# arduino-nano-dcc-v2.net
KiCad netlist of a schematic drawn in EAGLE
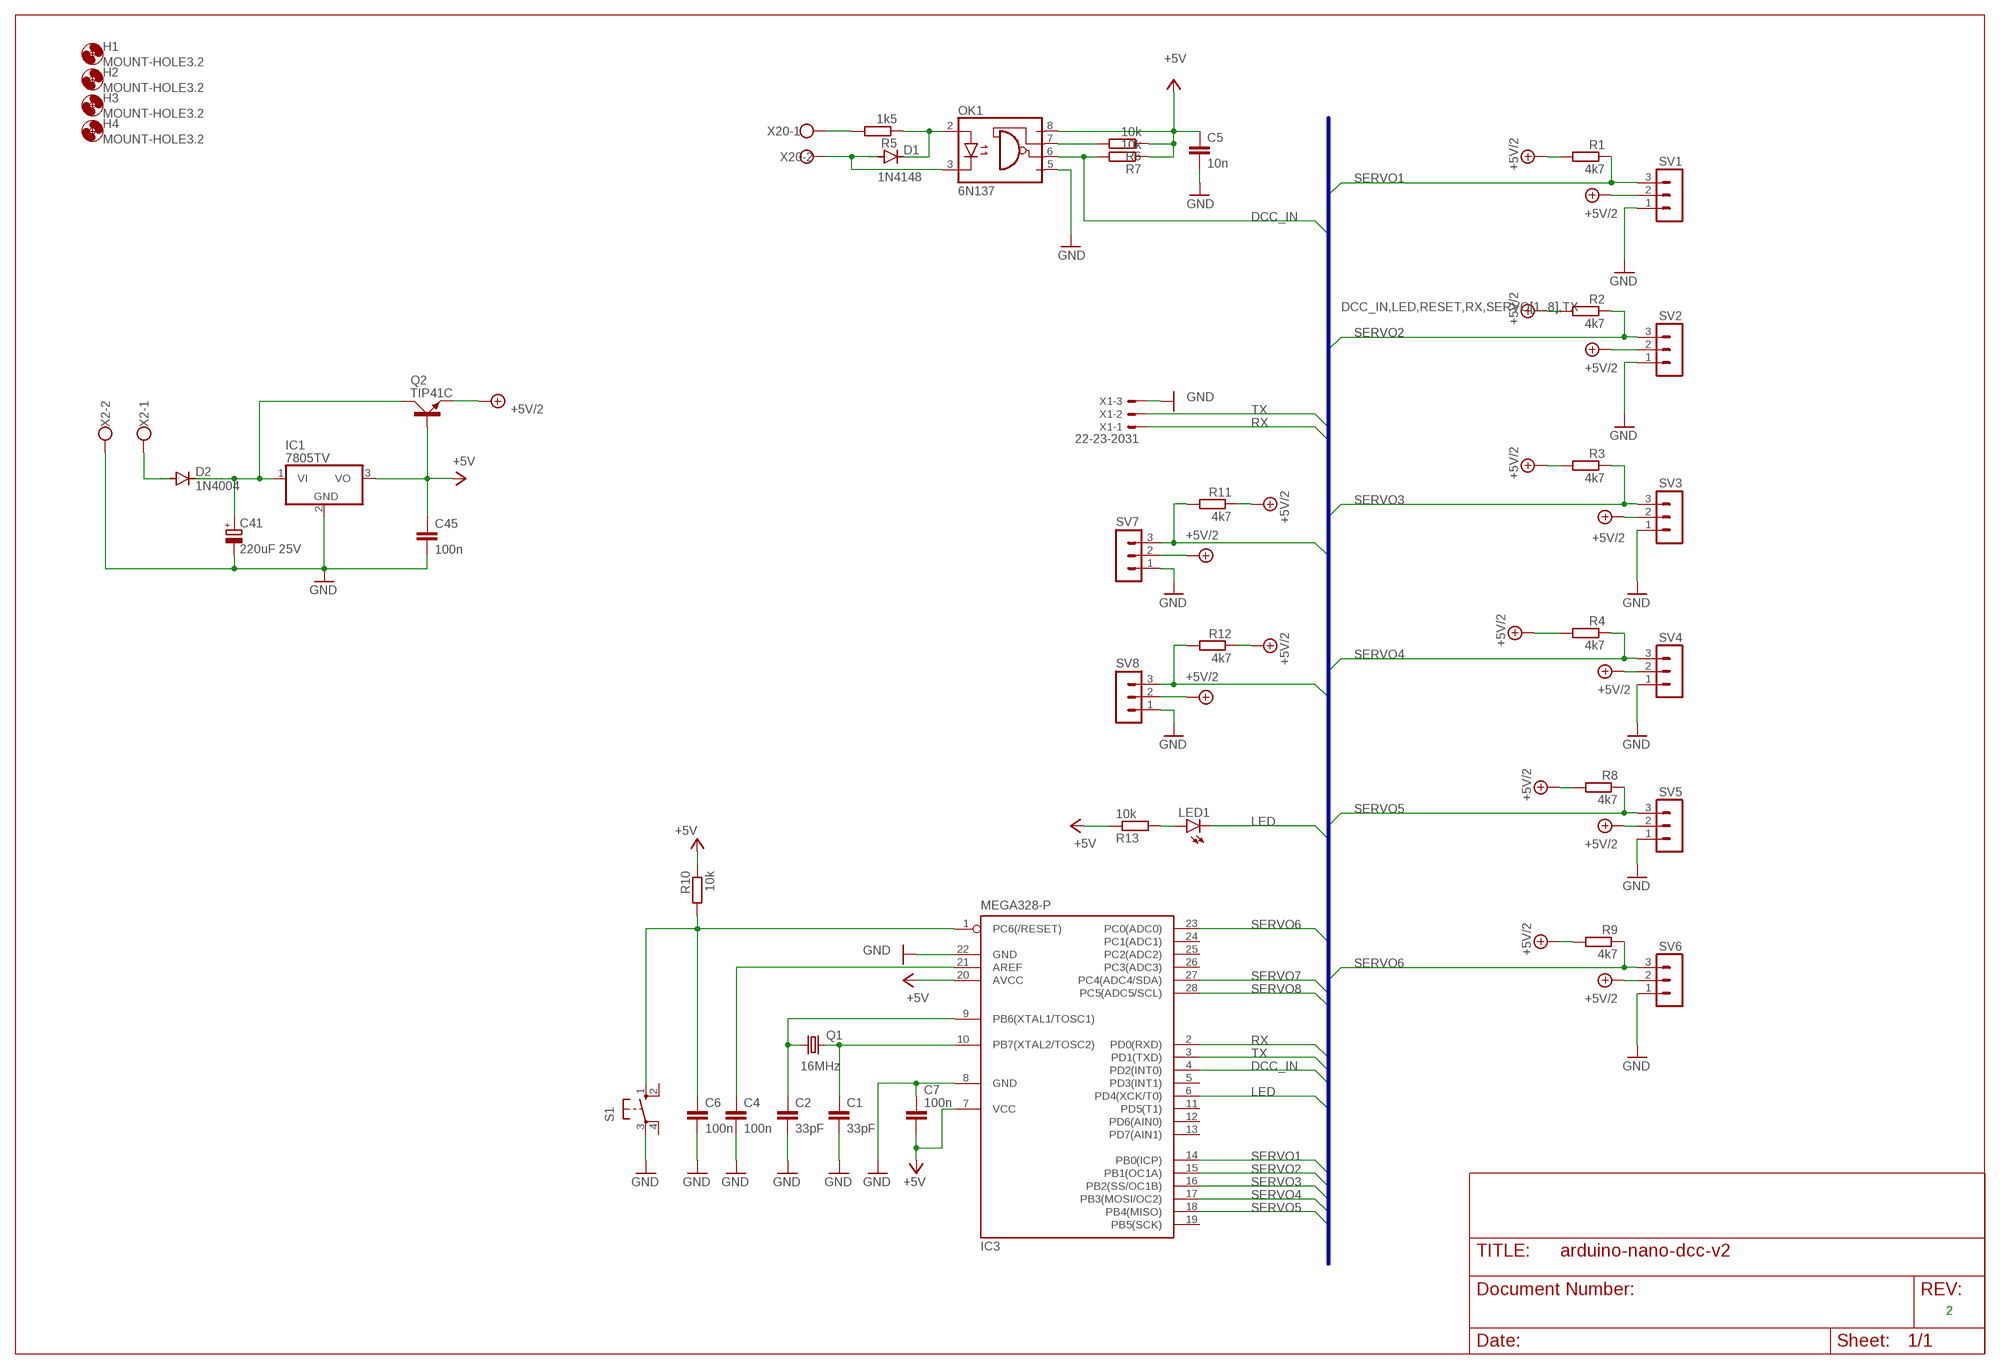
[diagram p0: schematic, sheet 1]

(export (version "E")
  (design (tool "Eeschema 10.0.6"))
  (components
    (comp (ref "C1")
      (value "33pF")
      (footprint "eagle-import:C025-024X044")
      (libsource (lib "eagle-import") (part "rcl_334_C-EU025-024X044"))
    )
    (comp (ref "C2")
      (value "33pF")
      (footprint "eagle-import:C025-024X044")
      (libsource (lib "eagle-import") (part "rcl_334_C-EU025-024X044"))
    )
    (comp (ref "C4")
      (value "100n")
      (footprint "eagle-import:C050-024X044")
      (libsource (lib "eagle-import") (part "rcl_334_C-EU050-024X044"))
    )
    (comp (ref "C5")
      (value "10n")
      (footprint "eagle-import:C050-024X044")
      (libsource (lib "eagle-import") (part "C-EU050-024X044"))
    )
    (comp (ref "C6")
      (value "100n")
      (footprint "eagle-import:C050-024X044")
      (libsource (lib "eagle-import") (part "rcl_334_C-EU050-024X044"))
    )
    (comp (ref "C7")
      (value "100n")
      (footprint "eagle-import:C050-024X044")
      (libsource (lib "eagle-import") (part "rcl_334_C-EU050-024X044"))
    )
    (comp (ref "C41")
      (value "220uF 25V")
      (footprint "eagle-import:E5-8,5")
      (libsource (lib "eagle-import") (part "CPOL-EUE5-8.5"))
    )
    (comp (ref "C45")
      (value "100n")
      (footprint "eagle-import:C050-024X044")
      (libsource (lib "eagle-import") (part "C-EU050-024X044"))
    )
    (comp (ref "D1")
      (value "1N4148")
      (footprint "eagle-import:DO35-7")
      (libsource (lib "eagle-import") (part "1N4148DO35-7"))
    )
    (comp (ref "D2")
      (value "1N4004")
      (footprint "eagle-import:DO41-10")
      (libsource (lib "eagle-import") (part "1N4004"))
    )
    (comp (ref "H1")
      (value "MOUNT-HOLE3.2")
      (footprint "eagle-import:3,2")
      (libsource (lib "eagle-import") (part "MOUNT-HOLE3.2"))
    )
    (comp (ref "H2")
      (value "MOUNT-HOLE3.2")
      (footprint "eagle-import:3,2")
      (libsource (lib "eagle-import") (part "MOUNT-HOLE3.2"))
    )
    (comp (ref "H3")
      (value "MOUNT-HOLE3.2")
      (footprint "eagle-import:3,2")
      (libsource (lib "eagle-import") (part "MOUNT-HOLE3.2"))
    )
    (comp (ref "H4")
      (value "MOUNT-HOLE3.2")
      (footprint "eagle-import:3,2")
      (libsource (lib "eagle-import") (part "MOUNT-HOLE3.2"))
    )
    (comp (ref "IC1")
      (value "7805TV")
      (footprint "eagle-import:TO220V")
      (libsource (lib "eagle-import") (part "78TV05"))
    )
    (comp (ref "IC3")
      (value "MEGA328-P")
      (footprint "eagle-import:DIL28-3")
      (libsource (lib "eagle-import") (part "MEGA8-P"))
    )
    (comp (ref "LED1")
      (value "LED3MM")
      (footprint "eagle-import:LED3MM")
      (libsource (lib "eagle-import") (part "LED3MM"))
    )
    (comp (ref "OK1")
      (value "6N137")
      (footprint "eagle-import:DIL08")
      (libsource (lib "eagle-import") (part "6N137"))
    )
    (comp (ref "Q1")
      (value "16MHz")
      (footprint "eagle-import:HC49U-V")
      (libsource (lib "eagle-import") (part "CRYSTALHC49U-V"))
    )
    (comp (ref "Q2")
      (value "TIP41C")
      (footprint "eagle-import:TO220AV")
      (libsource (lib "eagle-import") (part "TIP41C"))
    )
    (comp (ref "R1")
      (value "4k7")
      (footprint "eagle-import:0204_7")
      (libsource (lib "eagle-import") (part "R-EU_0204/7"))
    )
    (comp (ref "R2")
      (value "4k7")
      (footprint "eagle-import:0204_7")
      (libsource (lib "eagle-import") (part "R-EU_0204/7"))
    )
    (comp (ref "R3")
      (value "4k7")
      (footprint "eagle-import:0204_7")
      (libsource (lib "eagle-import") (part "R-EU_0204/7"))
    )
    (comp (ref "R4")
      (value "4k7")
      (footprint "eagle-import:0204_7")
      (libsource (lib "eagle-import") (part "R-EU_0204/7"))
    )
    (comp (ref "R5")
      (value "1k5")
      (footprint "eagle-import:0204_7")
      (libsource (lib "eagle-import") (part "R-EU_0204/7"))
    )
    (comp (ref "R6")
      (value "10k")
      (footprint "eagle-import:0204_7")
      (libsource (lib "eagle-import") (part "R-EU_0204/7"))
    )
    (comp (ref "R7")
      (value "10k")
      (footprint "eagle-import:0204_7")
      (libsource (lib "eagle-import") (part "R-EU_0204/7"))
    )
    (comp (ref "R8")
      (value "4k7")
      (footprint "eagle-import:0204_7")
      (libsource (lib "eagle-import") (part "R-EU_0204/7"))
    )
    (comp (ref "R9")
      (value "4k7")
      (footprint "eagle-import:0204_7")
      (libsource (lib "eagle-import") (part "R-EU_0204/7"))
    )
    (comp (ref "R10")
      (value "10k")
      (footprint "eagle-import:0204_7")
      (libsource (lib "eagle-import") (part "R-EU_0204/7"))
    )
    (comp (ref "R11")
      (value "4k7")
      (footprint "eagle-import:0204_7")
      (libsource (lib "eagle-import") (part "R-EU_0204/7"))
    )
    (comp (ref "R12")
      (value "4k7")
      (footprint "eagle-import:0204_5")
      (libsource (lib "eagle-import") (part "R-EU_0204/5"))
    )
    (comp (ref "R13")
      (value "10k")
      (footprint "eagle-import:0204V")
      (libsource (lib "eagle-import") (part "R-EU_0204/2V"))
    )
    (comp (ref "S1")
      (value "10-XX")
      (footprint "eagle-import:B3F-10XX")
      (fields (field (name "MPN") "B3F-1000"))
      (libsource (lib "eagle-import") (part "10-XX"))
    )
    (comp (ref "SV1")
      (value "MA03-1")
      (footprint "eagle-import:MA03-1")
      (libsource (lib "eagle-import") (part "MA03-1"))
    )
    (comp (ref "SV2")
      (value "MA03-1")
      (footprint "eagle-import:MA03-1")
      (libsource (lib "eagle-import") (part "MA03-1"))
    )
    (comp (ref "SV3")
      (value "MA03-1")
      (footprint "eagle-import:MA03-1")
      (libsource (lib "eagle-import") (part "MA03-1"))
    )
    (comp (ref "SV4")
      (value "MA03-1")
      (footprint "eagle-import:MA03-1")
      (libsource (lib "eagle-import") (part "MA03-1"))
    )
    (comp (ref "SV5")
      (value "MA03-1")
      (footprint "eagle-import:MA03-1")
      (libsource (lib "eagle-import") (part "MA03-1"))
    )
    (comp (ref "SV6")
      (value "MA03-1")
      (footprint "eagle-import:MA03-1")
      (libsource (lib "eagle-import") (part "MA03-1"))
    )
    (comp (ref "SV7")
      (value "MA03-1")
      (footprint "eagle-import:MA03-1")
      (libsource (lib "eagle-import") (part "MA03-1"))
    )
    (comp (ref "SV8")
      (value "MA03-1")
      (footprint "eagle-import:MA03-1")
      (libsource (lib "eagle-import") (part "MA03-1"))
    )
    (comp (ref "X1")
      (value "22-23-2031")
      (footprint "eagle-import:22-23-2031")
      (fields (field (name "MF") "MOLEX"))
      (libsource (lib "eagle-import") (part "22-23-2031"))
    )
    (comp (ref "X2")
      (value "W237-102")
      (footprint "eagle-import:W237-102")
      (fields (field (name "MPN") "237-102"))
      (libsource (lib "eagle-import") (part "W237-102"))
    )
    (comp (ref "X20")
      (value "W237-102")
      (footprint "eagle-import:W237-102")
      (fields (field (name "MPN") "237-102"))
      (libsource (lib "eagle-import") (part "W237-102"))
    )
  )
  (nets
    (net (code "2") (name "+5V") (class "Default")
      (node (ref "C45") (pin "1") (pinfunction "1_1") (pintype "passive"))
      (node (ref "C5") (pin "1") (pinfunction "1_1") (pintype "passive"))
      (node (ref "C7") (pin "2") (pinfunction "2_2") (pintype "passive"))
      (node (ref "IC1") (pin "3") (pinfunction "VO_3") (pintype "passive"))
      (node (ref "IC3") (pin "20") (pinfunction "AVCC_20") (pintype "power_in"))
      (node (ref "IC3") (pin "7") (pinfunction "VCC_7") (pintype "power_in"))
      (node (ref "OK1") (pin "8") (pinfunction "VCC_8") (pintype "passive"))
      (node (ref "Q2") (pin "B") (pinfunction "B_B") (pintype "passive"))
      (node (ref "R10") (pin "1") (pinfunction "1_1") (pintype "passive"))
      (node (ref "R13") (pin "1") (pinfunction "1_1") (pintype "passive"))
      (node (ref "R6") (pin "1") (pinfunction "1_1") (pintype "passive"))
      (node (ref "R7") (pin "1") (pinfunction "1_1") (pintype "passive"))
    )
    (net (code "3") (name "+5V{slash}2") (class "Default")
      (node (ref "Q2") (pin "E") (pinfunction "E_E") (pintype "passive"))
      (node (ref "R1") (pin "2") (pinfunction "2_2") (pintype "passive"))
      (node (ref "R11") (pin "1") (pinfunction "1_1") (pintype "passive"))
      (node (ref "R12") (pin "1") (pinfunction "1_1") (pintype "passive"))
      (node (ref "R2") (pin "2") (pinfunction "2_2") (pintype "passive"))
      (node (ref "R3") (pin "2") (pinfunction "2_2") (pintype "passive"))
      (node (ref "R4") (pin "2") (pinfunction "2_2") (pintype "passive"))
      (node (ref "R8") (pin "2") (pinfunction "2_2") (pintype "passive"))
      (node (ref "R9") (pin "2") (pinfunction "2_2") (pintype "passive"))
      (node (ref "SV1") (pin "2") (pinfunction "2_2") (pintype "passive"))
      (node (ref "SV2") (pin "2") (pinfunction "2_2") (pintype "passive"))
      (node (ref "SV3") (pin "2") (pinfunction "2_2") (pintype "passive"))
      (node (ref "SV4") (pin "2") (pinfunction "2_2") (pintype "passive"))
      (node (ref "SV5") (pin "2") (pinfunction "2_2") (pintype "passive"))
      (node (ref "SV6") (pin "2") (pinfunction "2_2") (pintype "passive"))
      (node (ref "SV7") (pin "2") (pinfunction "2_2") (pintype "passive"))
      (node (ref "SV8") (pin "2") (pinfunction "2_2") (pintype "passive"))
    )
    (net (code "4") (name "/DCC_IN") (class "Default")
      (node (ref "IC3") (pin "4") (pinfunction "PD2(INT0)_4") (pintype "bidirectional"))
      (node (ref "OK1") (pin "6") (pinfunction "VO_6") (pintype "passive"))
      (node (ref "R7") (pin "2") (pinfunction "2_2") (pintype "passive"))
    )
    (net (code "5") (name "/LED") (class "Default")
      (node (ref "IC3") (pin "6") (pinfunction "PD4(XCK/T0)_6") (pintype "bidirectional"))
      (node (ref "LED1") (pin "K") (pinfunction "C_K") (pintype "passive"))
    )
    (net (code "6") (name "/RX") (class "Default")
      (node (ref "IC3") (pin "2") (pinfunction "PD0(RXD)_2") (pintype "bidirectional"))
      (node (ref "X1") (pin "1") (pinfunction "S_1") (pintype "passive"))
    )
    (net (code "7") (name "/SERVO1") (class "Default")
      (node (ref "IC3") (pin "14") (pinfunction "PB0(ICP)_14") (pintype "bidirectional"))
      (node (ref "R1") (pin "1") (pinfunction "1_1") (pintype "passive"))
      (node (ref "SV1") (pin "3") (pinfunction "3_3") (pintype "passive"))
    )
    (net (code "8") (name "/SERVO2") (class "Default")
      (node (ref "IC3") (pin "15") (pinfunction "PB1(OC1A)_15") (pintype "bidirectional"))
      (node (ref "R2") (pin "1") (pinfunction "1_1") (pintype "passive"))
      (node (ref "SV2") (pin "3") (pinfunction "3_3") (pintype "passive"))
    )
    (net (code "9") (name "/SERVO3") (class "Default")
      (node (ref "IC3") (pin "16") (pinfunction "PB2(SS/OC1B)_16") (pintype "bidirectional"))
      (node (ref "R3") (pin "1") (pinfunction "1_1") (pintype "passive"))
      (node (ref "SV3") (pin "3") (pinfunction "3_3") (pintype "passive"))
    )
    (net (code "10") (name "/SERVO4") (class "Default")
      (node (ref "IC3") (pin "17") (pinfunction "PB3(MOSI/OC2)_17") (pintype "bidirectional"))
      (node (ref "R4") (pin "1") (pinfunction "1_1") (pintype "passive"))
      (node (ref "SV4") (pin "3") (pinfunction "3_3") (pintype "passive"))
    )
    (net (code "11") (name "/SERVO5") (class "Default")
      (node (ref "IC3") (pin "18") (pinfunction "PB4(MISO)_18") (pintype "bidirectional"))
      (node (ref "R8") (pin "1") (pinfunction "1_1") (pintype "passive"))
      (node (ref "SV5") (pin "3") (pinfunction "3_3") (pintype "passive"))
    )
    (net (code "12") (name "/SERVO6") (class "Default")
      (node (ref "IC3") (pin "23") (pinfunction "PC0(ADC0)_23") (pintype "bidirectional"))
      (node (ref "R9") (pin "1") (pinfunction "1_1") (pintype "passive"))
      (node (ref "SV6") (pin "3") (pinfunction "3_3") (pintype "passive"))
    )
    (net (code "13") (name "/SERVO7") (class "Default")
      (node (ref "IC3") (pin "27") (pinfunction "PC4(ADC4/SDA)_27") (pintype "bidirectional"))
      (node (ref "R11") (pin "2") (pinfunction "2_2") (pintype "passive"))
      (node (ref "SV7") (pin "3") (pinfunction "3_3") (pintype "passive"))
    )
    (net (code "14") (name "/SERVO8") (class "Default")
      (node (ref "IC3") (pin "28") (pinfunction "PC5(ADC5/SCL)_28") (pintype "bidirectional"))
      (node (ref "R12") (pin "2") (pinfunction "2_2") (pintype "passive"))
      (node (ref "SV8") (pin "3") (pinfunction "3_3") (pintype "passive"))
    )
    (net (code "15") (name "/TX") (class "Default")
      (node (ref "IC3") (pin "3") (pinfunction "PD1(TXD)_3") (pintype "bidirectional"))
      (node (ref "X1") (pin "2") (pinfunction "S_2") (pintype "passive"))
    )
    (net (code "17") (name "GND") (class "Default")
      (node (ref "C1") (pin "2") (pinfunction "2_2") (pintype "passive"))
      (node (ref "C2") (pin "2") (pinfunction "2_2") (pintype "passive"))
      (node (ref "C4") (pin "2") (pinfunction "2_2") (pintype "passive"))
      (node (ref "C41") (pin "-") (pinfunction "-_-") (pintype "passive"))
      (node (ref "C45") (pin "2") (pinfunction "2_2") (pintype "passive"))
      (node (ref "C5") (pin "2") (pinfunction "2_2") (pintype "passive"))
      (node (ref "C6") (pin "2") (pinfunction "2_2") (pintype "passive"))
      (node (ref "C7") (pin "1") (pinfunction "1_1") (pintype "passive"))
      (node (ref "IC1") (pin "2") (pinfunction "GND_2") (pintype "passive"))
      (node (ref "IC3") (pin "22") (pinfunction "GND_22") (pintype "power_in"))
      (node (ref "IC3") (pin "8") (pinfunction "GND_8") (pintype "power_in"))
      (node (ref "OK1") (pin "5") (pinfunction "GND_5") (pintype "passive"))
      (node (ref "S1") (pin "3") (pinfunction "P_3") (pintype "passive"))
      (node (ref "SV1") (pin "1") (pinfunction "1_1") (pintype "passive"))
      (node (ref "SV2") (pin "1") (pinfunction "1_1") (pintype "passive"))
      (node (ref "SV3") (pin "1") (pinfunction "1_1") (pintype "passive"))
      (node (ref "SV4") (pin "1") (pinfunction "1_1") (pintype "passive"))
      (node (ref "SV5") (pin "1") (pinfunction "1_1") (pintype "passive"))
      (node (ref "SV6") (pin "1") (pinfunction "1_1") (pintype "passive"))
      (node (ref "SV7") (pin "1") (pinfunction "1_1") (pintype "passive"))
      (node (ref "SV8") (pin "1") (pinfunction "1_1") (pintype "passive"))
      (node (ref "X1") (pin "3") (pinfunction "S_3") (pintype "passive"))
      (node (ref "X2") (pin "2") (pinfunction "KL_2") (pintype "passive"))
    )
    (net (code "18") (name "Net-(IC1-VI)") (class "Default")
      (node (ref "C41") (pin "+") (pinfunction "+_+") (pintype "passive"))
      (node (ref "D2") (pin "C") (pinfunction "C_C") (pintype "passive"))
      (node (ref "IC1") (pin "1") (pinfunction "VI_1") (pintype "input"))
      (node (ref "Q2") (pin "C") (pinfunction "C_C") (pintype "passive"))
    )
    (net (code "19") (name "Net-(IC3-AREF)") (class "Default")
      (node (ref "C4") (pin "1") (pinfunction "1_1") (pintype "passive"))
      (node (ref "IC3") (pin "21") (pinfunction "AREF_21") (pintype "passive"))
    )
    (net (code "20") (name "Net-(IC3-PB6(XTAL1{slash}TOSC1))") (class "Default")
      (node (ref "C2") (pin "1") (pinfunction "1_1") (pintype "passive"))
      (node (ref "IC3") (pin "9") (pinfunction "PB6(XTAL1/TOSC1)_9") (pintype "bidirectional"))
      (node (ref "Q1") (pin "1") (pinfunction "1_1") (pintype "passive"))
    )
    (net (code "21") (name "Net-(IC3-PB7(XTAL2{slash}TOSC2))") (class "Default")
      (node (ref "C1") (pin "1") (pinfunction "1_1") (pintype "passive"))
      (node (ref "IC3") (pin "10") (pinfunction "PB7(XTAL2/TOSC2)_10") (pintype "bidirectional"))
      (node (ref "Q1") (pin "2") (pinfunction "2_2") (pintype "passive"))
    )
    (net (code "22") (name "Net-(IC3-PC6({slash}RESET))") (class "Default")
      (node (ref "C6") (pin "1") (pinfunction "1_1") (pintype "passive"))
      (node (ref "IC3") (pin "1") (pinfunction "PC6(/RESET)_1") (pintype "bidirectional"))
      (node (ref "R10") (pin "2") (pinfunction "2_2") (pintype "passive"))
      (node (ref "S1") (pin "1") (pinfunction "S_1") (pintype "passive"))
    )
    (net (code "23") (name "Net-(LED1-PadA)") (class "Default")
      (node (ref "LED1") (pin "A") (pinfunction "A_A") (pintype "passive"))
      (node (ref "R13") (pin "2") (pinfunction "2_2") (pintype "passive"))
    )
    (net (code "24") (name "Net-(OK1-A)") (class "Default")
      (node (ref "D1") (pin "C") (pinfunction "C_C") (pintype "passive"))
      (node (ref "OK1") (pin "2") (pinfunction "A_2") (pintype "passive"))
      (node (ref "R5") (pin "1") (pinfunction "1_1") (pintype "passive"))
    )
    (net (code "25") (name "Net-(OK1-C)") (class "Default")
      (node (ref "D1") (pin "A") (pinfunction "A_A") (pintype "passive"))
      (node (ref "OK1") (pin "3") (pinfunction "C_3") (pintype "passive"))
      (node (ref "X20") (pin "2") (pinfunction "KL_2") (pintype "passive"))
    )
    (net (code "26") (name "Net-(OK1-VE)") (class "Default")
      (node (ref "OK1") (pin "7") (pinfunction "VE_7") (pintype "passive"))
      (node (ref "R6") (pin "2") (pinfunction "2_2") (pintype "passive"))
    )
    (net (code "27") (name "Net-(X2A-KL)") (class "Default")
      (node (ref "D2") (pin "A") (pinfunction "A_A") (pintype "passive"))
      (node (ref "X2") (pin "1") (pinfunction "KL_1") (pintype "passive"))
    )
    (net (code "28") (name "Net-(X20A-KL)") (class "Default")
      (node (ref "R5") (pin "2") (pinfunction "2_2") (pintype "passive"))
      (node (ref "X20") (pin "1") (pinfunction "KL_1") (pintype "passive"))
    )
    (net (code "29") (name "unconnected-(IC3-PB5(SCK)-Pad19)") (class "Default")
      (node (ref "IC3") (pin "19") (pinfunction "PB5(SCK)_19") (pintype "bidirectional"))
    )
    (net (code "30") (name "unconnected-(IC3-PC1(ADC1)-Pad24)") (class "Default")
      (node (ref "IC3") (pin "24") (pinfunction "PC1(ADC1)_24") (pintype "bidirectional"))
    )
    (net (code "31") (name "unconnected-(IC3-PC2(ADC2)-Pad25)") (class "Default")
      (node (ref "IC3") (pin "25") (pinfunction "PC2(ADC2)_25") (pintype "bidirectional"))
    )
    (net (code "32") (name "unconnected-(IC3-PC3(ADC3)-Pad26)") (class "Default")
      (node (ref "IC3") (pin "26") (pinfunction "PC3(ADC3)_26") (pintype "bidirectional"))
    )
    (net (code "33") (name "unconnected-(IC3-PD3(INT1)-Pad5)") (class "Default")
      (node (ref "IC3") (pin "5") (pinfunction "PD3(INT1)_5") (pintype "bidirectional"))
    )
    (net (code "34") (name "unconnected-(IC3-PD5(T1)-Pad11)") (class "Default")
      (node (ref "IC3") (pin "11") (pinfunction "PD5(T1)_11") (pintype "bidirectional"))
    )
    (net (code "35") (name "unconnected-(IC3-PD6(AIN0)-Pad12)") (class "Default")
      (node (ref "IC3") (pin "12") (pinfunction "PD6(AIN0)_12") (pintype "bidirectional"))
    )
    (net (code "36") (name "unconnected-(IC3-PD7(AIN1)-Pad13)") (class "Default")
      (node (ref "IC3") (pin "13") (pinfunction "PD7(AIN1)_13") (pintype "bidirectional"))
    )
    (net (code "37") (name "unconnected-(S1-P1-Pad4)") (class "Default")
      (node (ref "S1") (pin "4") (pinfunction "P1_4") (pintype "passive"))
    )
    (net (code "38") (name "unconnected-(S1-S1-Pad2)") (class "Default")
      (node (ref "S1") (pin "2") (pinfunction "S1_2") (pintype "passive"))
    )
  )
)
